# design_v2.net
KiCad netlist of a schematic drawn in EAGLE
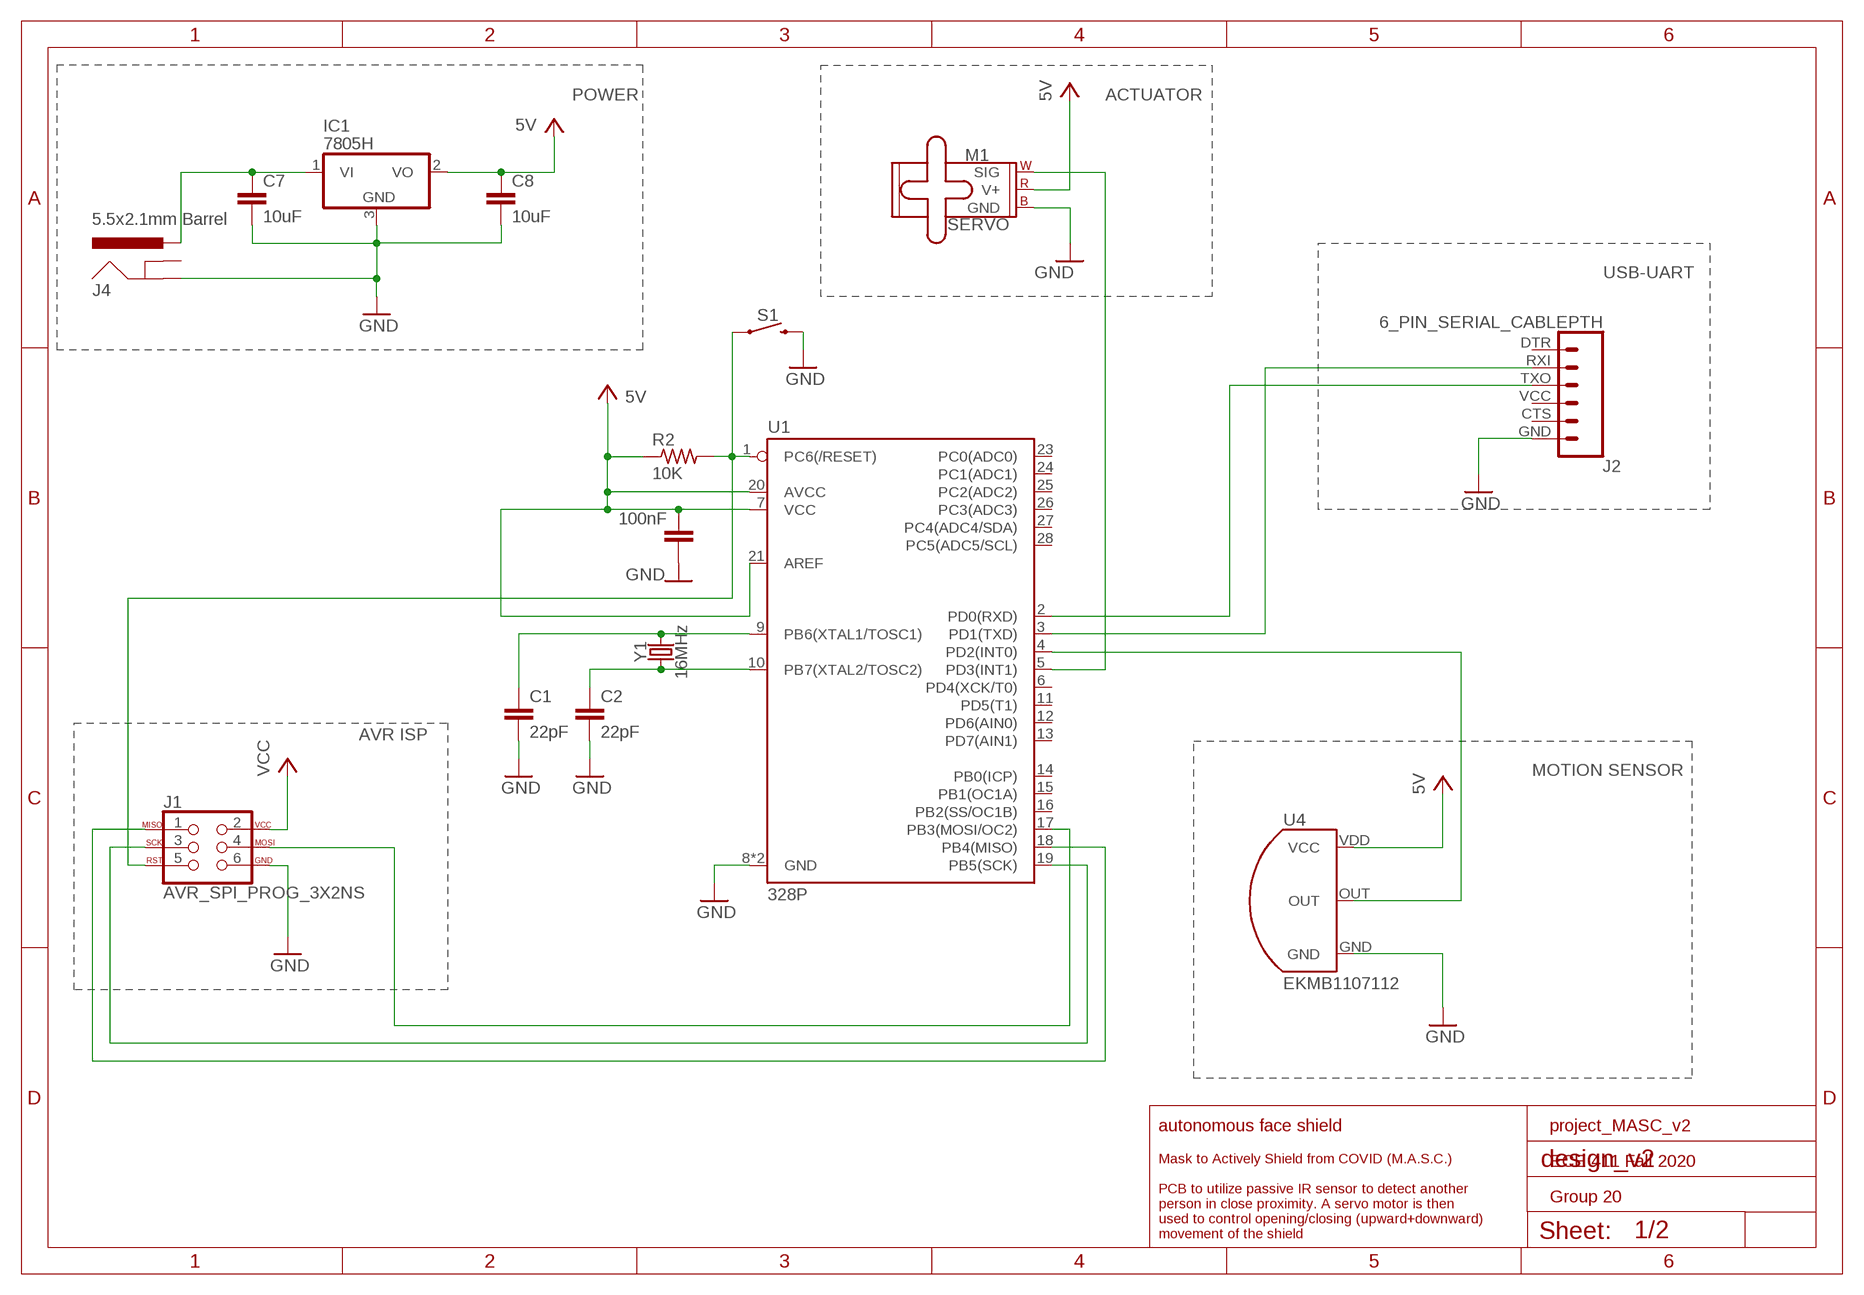
[diagram p0: schematic, sheet 1]

(export (version "E")
  (design (tool "Eeschema 10.0.6"))
  (components
    (comp (ref "C1")
      (value "22pF")
      (footprint "eagle-import:0805")
      (libsource (lib "eagle-import") (part "CAP-0805"))
    )
    (comp (ref "C2")
      (value "22pF")
      (footprint "eagle-import:0805")
      (libsource (lib "eagle-import") (part "CAP-0805"))
    )
    (comp (ref "C3")
      (value "100nF")
      (footprint "eagle-import:0805")
      (libsource (lib "eagle-import") (part "CAP-0805"))
    )
    (comp (ref "C7")
      (value "10uF")
      (footprint "eagle-import:0805")
      (libsource (lib "eagle-import") (part "CAP-0805"))
    )
    (comp (ref "C8")
      (value "10uF")
      (footprint "eagle-import:0805")
      (libsource (lib "eagle-import") (part "CAP-0805"))
    )
    (comp (ref "IC1")
      (value "7805H")
      (footprint "eagle-import:TO39")
      (libsource (lib "eagle-import") (part "78H05"))
    )
    (comp (ref "J1")
      (value "AVR_SPI_PROG_3X2NS")
      (footprint "eagle-import:2X3-NS")
      (libsource (lib "eagle-import") (part "AVR_SPI_PROG_3X2NS"))
    )
    (comp (ref "J2")
      (value "6_PIN_SERIAL_CABLEPTH")
      (footprint "eagle-import:FTDI_BASIC")
      (libsource (lib "eagle-import") (part "6_PIN_SERIAL_CABLEPTH"))
    )
    (comp (ref "J4")
      (value "5.5x2.1mm Barrel")
      (footprint "eagle-import:POWER_JACK_SMD")
      (libsource (lib "eagle-import") (part "POWER_JACKSMD"))
    )
    (comp (ref "M1")
      (value "SERVO")
      (footprint "eagle-import:1X03")
      (libsource (lib "eagle-import") (part "SERVO"))
    )
    (comp (ref "R2")
      (value "10K")
      (footprint "eagle-import:R0805")
      (libsource (lib "eagle-import") (part "R-US_R0805"))
    )
    (comp (ref "S1")
      (value "MOMENTARY-SWITCH-SPST-PTH-6.0MM")
      (footprint "eagle-import:TACTILE_SWITCH_PTH_6.0MM")
      (libsource (lib "eagle-import") (part "MOMENTARY-SWITCH-SPST-PTH-6.0MM"))
    )
    (comp (ref "U1")
      (value "328P")
      (footprint "eagle-import:DIP28")
      (libsource (lib "eagle-import") (part "ATMEGA328P_PDIP"))
    )
    (comp (ref "U4")
      (value "EKMB1107112")
      (footprint "eagle-import:TO-3")
      (libsource (lib "eagle-import") (part "PIR_EKMB1107112"))
    )
    (comp (ref "Y1")
      (value "16MHz")
      (footprint "eagle-import:HC49US")
      (libsource (lib "eagle-import") (part "CRYSTAL-16MHZPTH-HC49US"))
    )
  )
  (nets
    (net (code "1") (name "GND") (class "Default")
      (node (ref "C1") (pin "2") (pinfunction "2_2") (pintype "passive"))
      (node (ref "C2") (pin "2") (pinfunction "2_2") (pintype "passive"))
      (node (ref "C3") (pin "1") (pinfunction "1_1") (pintype "passive"))
      (node (ref "C7") (pin "2") (pinfunction "2_2") (pintype "passive"))
      (node (ref "C8") (pin "2") (pinfunction "2_2") (pintype "passive"))
      (node (ref "IC1") (pin "3") (pinfunction "GND_3") (pintype "passive"))
      (node (ref "J1") (pin "6") (pinfunction "6_6") (pintype "passive"))
      (node (ref "J2") (pin "GND") (pinfunction "6_GND") (pintype "passive"))
      (node (ref "J4") (pin "P$4") (pinfunction "GND_P$4") (pintype "bidirectional"))
      (node (ref "M1") (pin "3") (pinfunction "GND_3") (pintype "bidirectional"))
      (node (ref "S1") (pin "3") (pinfunction "2_3") (pintype "passive"))
      (node (ref "U1") (pin "22") (pinfunction "GND_22") (pintype "bidirectional"))
      (node (ref "U1") (pin "8") (pinfunction "GND_8") (pintype "bidirectional"))
      (node (ref "U4") (pin "GND") (pinfunction "GND_GND") (pintype "bidirectional"))
    )
    (net (code "2") (name "Net-(IC1-VI)") (class "Default")
      (node (ref "C7") (pin "1") (pinfunction "1_1") (pintype "passive"))
      (node (ref "IC1") (pin "1") (pinfunction "VI_1") (pintype "input"))
      (node (ref "J4") (pin "VIN0") (pinfunction "PWR_VIN0") (pintype "bidirectional"))
    )
    (net (code "3") (name "Net-(J2-2)") (class "Default")
      (node (ref "J2") (pin "RXI") (pinfunction "2_RXI") (pintype "passive"))
      (node (ref "U1") (pin "3") (pinfunction "PD1(TXD)_3") (pintype "bidirectional"))
    )
    (net (code "4") (name "Net-(J2-3)") (class "Default")
      (node (ref "J2") (pin "TXO") (pinfunction "3_TXO") (pintype "passive"))
      (node (ref "U1") (pin "2") (pinfunction "PD0(RXD)_2") (pintype "bidirectional"))
    )
    (net (code "5") (name "Net-(M1-SIG)") (class "Default")
      (node (ref "M1") (pin "1") (pinfunction "SIG_1") (pintype "bidirectional"))
      (node (ref "U1") (pin "5") (pinfunction "PD3(INT1)_5") (pintype "bidirectional"))
    )
    (net (code "6") (name "Net-(U1-PB3(MOSI{slash}OC2))") (class "Default")
      (node (ref "J1") (pin "4") (pinfunction "4_4") (pintype "passive"))
      (node (ref "U1") (pin "17") (pinfunction "PB3(MOSI/OC2)_17") (pintype "bidirectional"))
    )
    (net (code "7") (name "Net-(U1-PB4(MISO))") (class "Default")
      (node (ref "J1") (pin "1") (pinfunction "1_1") (pintype "passive"))
      (node (ref "U1") (pin "18") (pinfunction "PB4(MISO)_18") (pintype "bidirectional"))
    )
    (net (code "8") (name "Net-(U1-PB5(SCK))") (class "Default")
      (node (ref "J1") (pin "3") (pinfunction "3_3") (pintype "passive"))
      (node (ref "U1") (pin "19") (pinfunction "PB5(SCK)_19") (pintype "bidirectional"))
    )
    (net (code "9") (name "Net-(U1-PB6(XTAL1{slash}TOSC1))") (class "Default")
      (node (ref "C1") (pin "1") (pinfunction "1_1") (pintype "passive"))
      (node (ref "U1") (pin "9") (pinfunction "PB6(XTAL1/TOSC1)_9") (pintype "bidirectional"))
      (node (ref "Y1") (pin "2") (pinfunction "2_2") (pintype "passive"))
    )
    (net (code "10") (name "Net-(U1-PB7(XTAL2{slash}TOSC2))") (class "Default")
      (node (ref "C2") (pin "1") (pinfunction "1_1") (pintype "passive"))
      (node (ref "U1") (pin "10") (pinfunction "PB7(XTAL2/TOSC2)_10") (pintype "bidirectional"))
      (node (ref "Y1") (pin "1") (pinfunction "1_1") (pintype "passive"))
    )
    (net (code "11") (name "Net-(U1-PC6({slash}RESET))") (class "Default")
      (node (ref "J1") (pin "5") (pinfunction "5_5") (pintype "passive"))
      (node (ref "R2") (pin "2") (pinfunction "2_2") (pintype "passive"))
      (node (ref "S1") (pin "1") (pinfunction "1_1") (pintype "passive"))
      (node (ref "U1") (pin "1") (pinfunction "PC6(/RESET)_1") (pintype "bidirectional"))
    )
    (net (code "12") (name "Net-(U1-PD2(INT0))") (class "Default")
      (node (ref "U1") (pin "4") (pinfunction "PD2(INT0)_4") (pintype "bidirectional"))
      (node (ref "U4") (pin "OUT") (pinfunction "OUT_OUT") (pintype "bidirectional"))
    )
    (net (code "13") (name "VCC") (class "Default")
      (node (ref "C3") (pin "2") (pinfunction "2_2") (pintype "passive"))
      (node (ref "C8") (pin "1") (pinfunction "1_1") (pintype "passive"))
      (node (ref "IC1") (pin "2") (pinfunction "VO_2") (pintype "passive"))
      (node (ref "J1") (pin "2") (pinfunction "2_2") (pintype "passive"))
      (node (ref "M1") (pin "2") (pinfunction "V+_2") (pintype "bidirectional"))
      (node (ref "R2") (pin "1") (pinfunction "1_1") (pintype "passive"))
      (node (ref "U1") (pin "20") (pinfunction "AVCC_20") (pintype "bidirectional"))
      (node (ref "U1") (pin "21") (pinfunction "AREF_21") (pintype "bidirectional"))
      (node (ref "U1") (pin "7") (pinfunction "VCC_7") (pintype "bidirectional"))
      (node (ref "U4") (pin "VDD") (pinfunction "VCC_VDD") (pintype "bidirectional"))
    )
    (net (code "14") (name "unconnected-(J2-1-PadDTR)") (class "Default")
      (node (ref "J2") (pin "DTR") (pinfunction "1_DTR") (pintype "passive"))
    )
    (net (code "15") (name "unconnected-(J2-4-PadVCC)") (class "Default")
      (node (ref "J2") (pin "VCC") (pinfunction "4_VCC") (pintype "passive"))
    )
    (net (code "16") (name "unconnected-(J2-5-PadCTS)") (class "Default")
      (node (ref "J2") (pin "CTS") (pinfunction "5_CTS") (pintype "passive"))
    )
    (net (code "17") (name "unconnected-(J4-GNDBREAK-PadGND)") (class "Default")
      (node (ref "J4") (pin "GND") (pinfunction "GNDBREAK_GND") (pintype "bidirectional"))
    )
    (net (code "18") (name "unconnected-(U1-PB0(ICP)-Pad14)") (class "Default")
      (node (ref "U1") (pin "14") (pinfunction "PB0(ICP)_14") (pintype "bidirectional"))
    )
    (net (code "19") (name "unconnected-(U1-PB1(OC1A)-Pad15)") (class "Default")
      (node (ref "U1") (pin "15") (pinfunction "PB1(OC1A)_15") (pintype "bidirectional"))
    )
    (net (code "20") (name "unconnected-(U1-PB2(SS{slash}OC1B)-Pad16)") (class "Default")
      (node (ref "U1") (pin "16") (pinfunction "PB2(SS/OC1B)_16") (pintype "bidirectional"))
    )
    (net (code "21") (name "unconnected-(U1-PC0(ADC0)-Pad23)") (class "Default")
      (node (ref "U1") (pin "23") (pinfunction "PC0(ADC0)_23") (pintype "bidirectional"))
    )
    (net (code "22") (name "unconnected-(U1-PC1(ADC1)-Pad24)") (class "Default")
      (node (ref "U1") (pin "24") (pinfunction "PC1(ADC1)_24") (pintype "bidirectional"))
    )
    (net (code "23") (name "unconnected-(U1-PC2(ADC2)-Pad25)") (class "Default")
      (node (ref "U1") (pin "25") (pinfunction "PC2(ADC2)_25") (pintype "bidirectional"))
    )
    (net (code "24") (name "unconnected-(U1-PC3(ADC3)-Pad26)") (class "Default")
      (node (ref "U1") (pin "26") (pinfunction "PC3(ADC3)_26") (pintype "bidirectional"))
    )
    (net (code "25") (name "unconnected-(U1-PC4(ADC4{slash}SDA)-Pad27)") (class "Default")
      (node (ref "U1") (pin "27") (pinfunction "PC4(ADC4/SDA)_27") (pintype "bidirectional"))
    )
    (net (code "26") (name "unconnected-(U1-PC5(ADC5{slash}SCL)-Pad28)") (class "Default")
      (node (ref "U1") (pin "28") (pinfunction "PC5(ADC5/SCL)_28") (pintype "bidirectional"))
    )
    (net (code "27") (name "unconnected-(U1-PD4(XCK{slash}T0)-Pad6)") (class "Default")
      (node (ref "U1") (pin "6") (pinfunction "PD4(XCK/T0)_6") (pintype "bidirectional"))
    )
    (net (code "28") (name "unconnected-(U1-PD5(T1)-Pad11)") (class "Default")
      (node (ref "U1") (pin "11") (pinfunction "PD5(T1)_11") (pintype "bidirectional"))
    )
    (net (code "29") (name "unconnected-(U1-PD6(AIN0)-Pad12)") (class "Default")
      (node (ref "U1") (pin "12") (pinfunction "PD6(AIN0)_12") (pintype "bidirectional"))
    )
    (net (code "30") (name "unconnected-(U1-PD7(AIN1)-Pad13)") (class "Default")
      (node (ref "U1") (pin "13") (pinfunction "PD7(AIN1)_13") (pintype "bidirectional"))
    )
  )
)
